# Power_management.net
KiCad netlist of a schematic drawn in Altium Designer
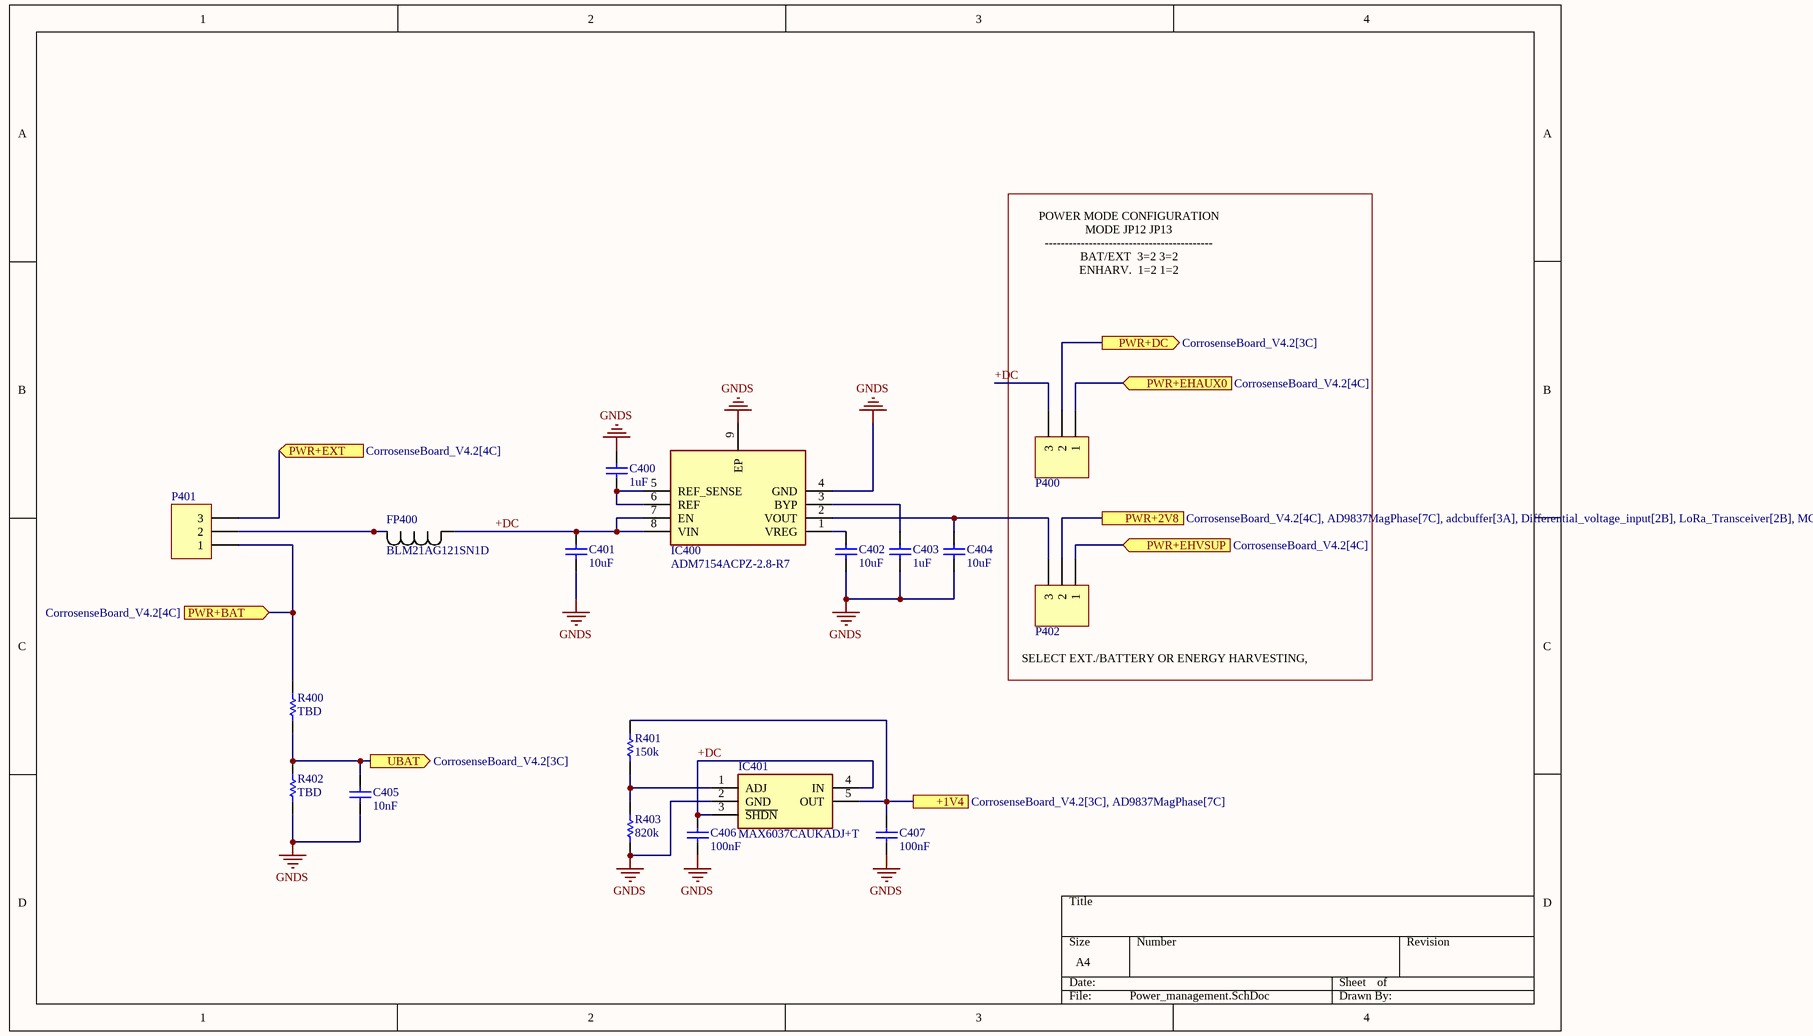
[diagram p0: Power_management.SchDoc]

(export (version "E")
  (design (tool "Eeschema 10.0.6"))
  (components
    (comp (ref "C400")
      (value "1uF")
      (footprint "1608[0603]")
      (description "CAP CER 25V X7R 0603")
      (fields (field (name "TOLERANCE") "±10%") (field (name "MANUFACTURER") "Murata Electronics"))
      (libsource (lib "Miscellaneous Devices") (part "Cap"))
    )
    (comp (ref "C401")
      (value "10uF")
      (footprint "1608[0603]")
      (description "CAP CER 25V X7R 0603")
      (fields (field (name "TOLERANCE") "±10%") (field (name "MANUFACTURER") "Murata Electronics"))
      (libsource (lib "Miscellaneous Devices") (part "Cap"))
    )
    (comp (ref "C402")
      (value "10uF")
      (footprint "1608[0603]")
      (description "CAP CER 25V X7R 0603")
      (fields (field (name "TOLERANCE") "±10%") (field (name "MANUFACTURER") "Murata Electronics"))
      (libsource (lib "Miscellaneous Devices") (part "Cap"))
    )
    (comp (ref "C403")
      (value "1uF")
      (footprint "1608[0603]")
      (description "CAP CER 25V X7R 0603")
      (fields (field (name "TOLERANCE") "±10%") (field (name "MANUFACTURER") "Murata Electronics"))
      (libsource (lib "Miscellaneous Devices") (part "Cap"))
    )
    (comp (ref "C404")
      (value "10uF")
      (footprint "1608[0603]")
      (description "CAP CER 25V X7R 0603")
      (fields (field (name "TOLERANCE") "±10%") (field (name "MANUFACTURER") "Murata Electronics"))
      (libsource (lib "Miscellaneous Devices") (part "Cap"))
    )
    (comp (ref "C405")
      (value "10nF")
      (footprint "1608[0603]")
      (description "CAP CER 25V X7R 0603")
      (fields (field (name "TOLERANCE") "±10%") (field (name "MANUFACTURER") "Murata Electronics"))
      (libsource (lib "Miscellaneous Devices") (part "Cap"))
    )
    (comp (ref "C406")
      (value "100nF")
      (footprint "1608[0603]")
      (description "CAP CER 25V X7R 0603")
      (fields (field (name "TOLERANCE") "±10%") (field (name "MANUFACTURER") "Murata Electronics"))
      (libsource (lib "Miscellaneous Devices") (part "Cap"))
    )
    (comp (ref "C407")
      (value "100nF")
      (footprint "1608[0603]")
      (description "CAP CER 25V X7R 0603")
      (fields (field (name "TOLERANCE") "±10%") (field (name "MANUFACTURER") "Murata Electronics"))
      (libsource (lib "Miscellaneous Devices") (part "Cap"))
    )
    (comp (ref "FP400")
      (value "BLM21AG121SN1D")
      (footprint "BEADC2012X105N")
      (description "No Description Available")
      (fields (field (name "MANUFACTURER") "Murata Electronics"))
      (libsource (lib "BLM21AG121SN1D") (part "BLM21AG121SN1D"))
    )
    (comp (ref "IC400")
      (value "ADM7154ACPZ-2.8-R7")
      (footprint "SamacSys:SON50P300X300X80-9N-D")
      (description "Integrated Circuit")
      (fields
        (field (name "MOUSER PART NUMBER") "584-ADM7154ACPZ2.8R7")
        (field (name "MANUFACTURER") "Analog Devices")
      )
      (libsource (lib "*") (part "ADM7154ACPZ-2.8-R7"))
    )
    (comp (ref "IC401")
      (value "MAX6037CAUKADJ+T")
      (footprint "SamacSys:SOT95P280X145-5N")
      (description "Integrated Circuit")
      (fields
        (field (name "MOUSER PART NUMBER") "700-MAX6037CAUKADJT")
        (field (name "MANUFACTURER") "Analog Devices")
      )
      (libsource (lib "*") (part "MAX6037CAUKADJ+T"))
    )
    (comp (ref "P400")
      (value "Header, 3-Pin")
      (footprint "HDR1X3")
      (fields
        (field (name "MANUFACTURER") "Wurth Elektronik")
        (field (name "MPN") "61300311121")
        (field (name "PUBLISHER") "Altium Limited")
      )
      (libsource (lib "Miscellaneous Connectors") (part "Header 3"))
    )
    (comp (ref "P401")
      (value "Header, 3-Pin")
      (footprint "HDR1X3")
      (fields
        (field (name "MANUFACTURER") "Wurth Elektronik")
        (field (name "MPN") "61300311121")
        (field (name "PUBLISHER") "Altium Limited")
      )
      (libsource (lib "") (part "Header 3_1"))
    )
    (comp (ref "P402")
      (value "Header, 3-Pin")
      (footprint "HDR1X3")
      (fields
        (field (name "MANUFACTURER") "Wurth Elektronik")
        (field (name "MPN") "61300311121")
        (field (name "PUBLISHER") "Altium Limited")
      )
      (libsource (lib "Miscellaneous Connectors") (part "Header 3"))
    )
    (comp (ref "R400")
      (value "TBD")
      (footprint "1608[0603]")
      (description "RES SMD 2% 1.5W 0603")
      (fields
        (field (name "MP") "-65°C ~ 155°C")
        (field (name "TOLERANCE") "2%")
        (field (name "PUBLISHER") "Altium Limited")
      )
      (libsource (lib "Res1") (part "Res1"))
    )
    (comp (ref "R401")
      (value "150k")
      (footprint "1608[0603]")
      (description "RES SMD 2% 1.5W 0603")
      (fields
        (field (name "MP") "-65°C ~ 155°C")
        (field (name "TOLERANCE") "2%")
        (field (name "PUBLISHER") "Altium Limited")
      )
      (libsource (lib "Res1") (part "Res1"))
    )
    (comp (ref "R402")
      (value "TBD")
      (footprint "1608[0603]")
      (description "RES SMD 2% 1.5W 0603")
      (fields
        (field (name "MP") "-65°C ~ 155°C")
        (field (name "TOLERANCE") "2%")
        (field (name "PUBLISHER") "Altium Limited")
      )
      (libsource (lib "Res1") (part "Res1"))
    )
    (comp (ref "R403")
      (value "820k")
      (footprint "1608[0603]")
      (description "RES SMD 2% 1.5W 0603")
      (fields
        (field (name "MP") "-65°C ~ 155°C")
        (field (name "TOLERANCE") "2%")
        (field (name "PUBLISHER") "Altium Limited")
      )
      (libsource (lib "Res1") (part "Res1"))
    )
  )
  (nets
    (net (code "1") (name "/+1V4") (class "Default")
      (node (ref "C407") (pin "1") (pinfunction "1_1") (pintype "passive"))
      (node (ref "IC401") (pin "5") (pinfunction "OUT_5") (pintype "passive"))
      (node (ref "R401") (pin "2") (pinfunction "2_2") (pintype "passive"))
    )
    (net (code "2") (name "/+DC") (class "Default")
      (node (ref "C401") (pin "1") (pinfunction "1_1") (pintype "passive"))
      (node (ref "C406") (pin "1") (pinfunction "1_1") (pintype "passive"))
      (node (ref "FP400") (pin "2") (pinfunction "2_2") (pintype "passive"))
      (node (ref "IC400") (pin "7") (pinfunction "EN_7") (pintype "passive"))
      (node (ref "IC400") (pin "8") (pinfunction "VIN_8") (pintype "passive"))
      (node (ref "IC401") (pin "3") (pinfunction "~{SHDN}_3") (pintype "passive"))
      (node (ref "IC401") (pin "4") (pinfunction "IN_4") (pintype "passive"))
      (node (ref "P400") (pin "3") (pinfunction "3_3") (pintype "passive"))
    )
    (net (code "3") (name "/PWR+2V8") (class "Default")
      (node (ref "P402") (pin "2") (pinfunction "2_2") (pintype "passive"))
    )
    (net (code "4") (name "/PWR+BAT") (class "Default")
      (node (ref "P401") (pin "1") (pinfunction "1_1") (pintype "passive"))
      (node (ref "R400") (pin "2") (pinfunction "2_2") (pintype "passive"))
    )
    (net (code "5") (name "/PWR+DC") (class "Default")
      (node (ref "P400") (pin "2") (pinfunction "2_2") (pintype "passive"))
    )
    (net (code "6") (name "/PWR+EHAUX0") (class "Default")
      (node (ref "P400") (pin "1") (pinfunction "1_1") (pintype "passive"))
    )
    (net (code "7") (name "/PWR+EHVSUP") (class "Default")
      (node (ref "P402") (pin "1") (pinfunction "1_1") (pintype "passive"))
    )
    (net (code "8") (name "/PWR+EXT") (class "Default")
      (node (ref "P401") (pin "3") (pinfunction "3_3") (pintype "passive"))
    )
    (net (code "9") (name "/UBAT") (class "Default")
      (node (ref "C405") (pin "2") (pinfunction "2_2") (pintype "passive"))
      (node (ref "R400") (pin "1") (pinfunction "1_1") (pintype "passive"))
      (node (ref "R402") (pin "2") (pinfunction "2_2") (pintype "passive"))
    )
    (net (code "10") (name "GNDS") (class "Default")
      (node (ref "C400") (pin "1") (pinfunction "1_1") (pintype "passive"))
      (node (ref "C401") (pin "2") (pinfunction "2_2") (pintype "passive"))
      (node (ref "C402") (pin "1") (pinfunction "1_1") (pintype "passive"))
      (node (ref "C403") (pin "2") (pinfunction "2_2") (pintype "passive"))
      (node (ref "C404") (pin "2") (pinfunction "2_2") (pintype "passive"))
      (node (ref "C405") (pin "1") (pinfunction "1_1") (pintype "passive"))
      (node (ref "C406") (pin "2") (pinfunction "2_2") (pintype "passive"))
      (node (ref "C407") (pin "2") (pinfunction "2_2") (pintype "passive"))
      (node (ref "IC400") (pin "4") (pinfunction "GND_4") (pintype "passive"))
      (node (ref "IC400") (pin "9") (pinfunction "EP_9") (pintype "passive"))
      (node (ref "IC401") (pin "2") (pinfunction "GND_2") (pintype "passive"))
      (node (ref "R402") (pin "1") (pinfunction "1_1") (pintype "passive"))
      (node (ref "R403") (pin "1") (pinfunction "1_1") (pintype "passive"))
    )
    (net (code "11") (name "Net-(FP400-Pad1)") (class "Default")
      (node (ref "FP400") (pin "1") (pinfunction "1_1") (pintype "passive"))
      (node (ref "P401") (pin "2") (pinfunction "2_2") (pintype "passive"))
    )
    (net (code "12") (name "Net-(IC400-BYP)") (class "Default")
      (node (ref "C403") (pin "1") (pinfunction "1_1") (pintype "passive"))
      (node (ref "IC400") (pin "3") (pinfunction "BYP_3") (pintype "passive"))
    )
    (net (code "13") (name "Net-(IC400-REF)") (class "Default")
      (node (ref "C400") (pin "2") (pinfunction "2_2") (pintype "passive"))
      (node (ref "IC400") (pin "5") (pinfunction "REF_SENSE_5") (pintype "passive"))
      (node (ref "IC400") (pin "6") (pinfunction "REF_6") (pintype "passive"))
    )
    (net (code "14") (name "Net-(IC400-VOUT)") (class "Default")
      (node (ref "C404") (pin "1") (pinfunction "1_1") (pintype "passive"))
      (node (ref "IC400") (pin "2") (pinfunction "VOUT_2") (pintype "passive"))
      (node (ref "P402") (pin "3") (pinfunction "3_3") (pintype "passive"))
    )
    (net (code "15") (name "Net-(IC400-VREG)") (class "Default")
      (node (ref "C402") (pin "2") (pinfunction "2_2") (pintype "passive"))
      (node (ref "IC400") (pin "1") (pinfunction "VREG_1") (pintype "passive"))
    )
    (net (code "16") (name "Net-(IC401-ADJ)") (class "Default")
      (node (ref "IC401") (pin "1") (pinfunction "ADJ_1") (pintype "passive"))
      (node (ref "R401") (pin "1") (pinfunction "1_1") (pintype "passive"))
      (node (ref "R403") (pin "2") (pinfunction "2_2") (pintype "passive"))
    )
  )
)
